# Sheet1-multi.net
KiCad netlist of a schematic drawn in Altium Designer
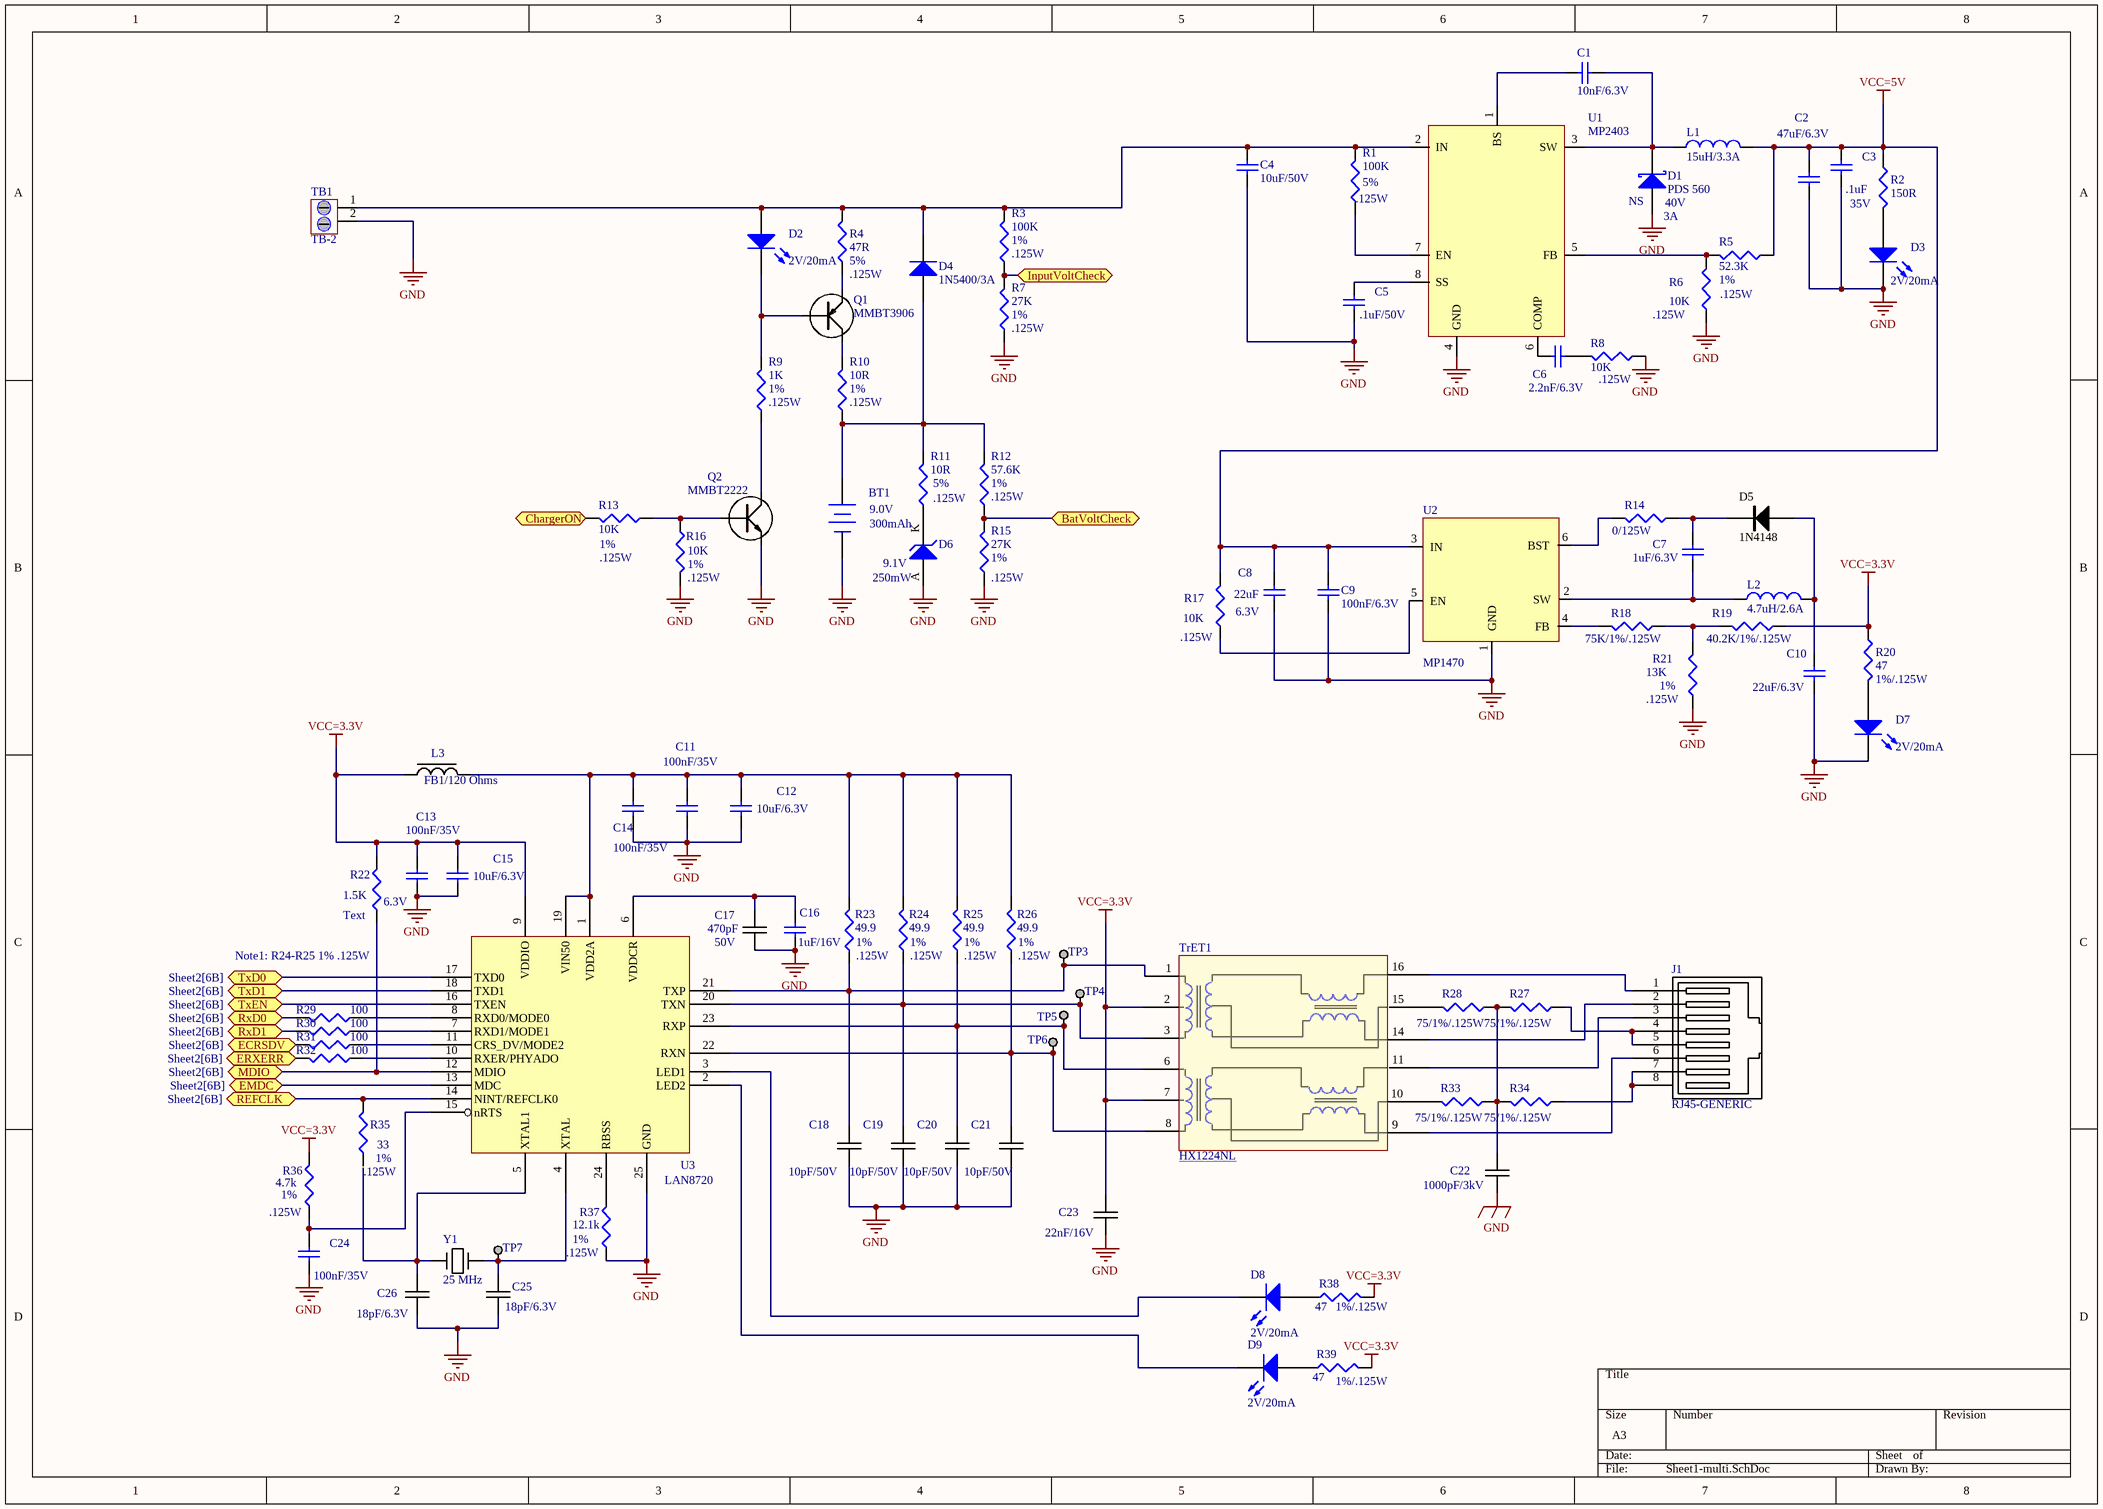
[diagram p0: Sheet1-multi.SchDoc]

(export (version "E")
  (design (tool "Eeschema 10.0.6"))
  (components
    (comp (ref "BT1")
      (value "9.0V")
      (footprint "BAT-2")
      (description "Multicell Battery")
      (fields
        (field (name "MANUFACTURER") "Guangdons China")
        (field (name "PUBLISHER") "sunbangpower.en.alibaba.com")
      )
      (libsource (lib "Miscellaneous Devices") (part "Battery"))
    )
    (comp (ref "C1")
      (value "10nF/6.3V")
      (footprint "0402C-GENERIC")
      (description "Capacitor")
      (fields (field (name "MANUFACTURER") "Murata") (field (name "PUBLISHER") "Altium Limited"))
      (libsource (lib "Miscellaneous Devices") (part "Cap"))
    )
    (comp (ref "C2")
      (value "47uF/6.3V")
      (footprint "1210C-GENERIC")
      (description "Capacitor")
      (fields (field (name "MANUFACTURER") "Murata") (field (name "PUBLISHER") "Altium Limited"))
      (libsource (lib "Miscellaneous Devices") (part "Cap"))
    )
    (comp (ref "C3")
      (value ".1uF")
      (footprint "0402C-GENERIC")
      (description "Capacitor")
      (fields (field (name "MANUFACTURER") "Yaiyo Yuden") (field (name "PUBLISHER") "Altium Limited"))
      (libsource (lib "Miscellaneous Devices") (part "Cap"))
    )
    (comp (ref "C4")
      (value "10uF/50V")
      (footprint "1206C-GENERIC")
      (description "Capacitor")
      (fields (field (name "MANUFACTURER") "Murata") (field (name "PUBLISHER") "Altium Limited"))
      (libsource (lib "Miscellaneous Devices") (part "Cap"))
    )
    (comp (ref "C5")
      (value ".1uF/50V")
      (footprint "0402C-GENERIC")
      (description "Capacitor")
      (fields (field (name "MANUFACTURER") "Murata") (field (name "PUBLISHER") "Altium Limited"))
      (libsource (lib "Miscellaneous Devices") (part "Cap"))
    )
    (comp (ref "C6")
      (value "2.2nF/6.3V")
      (footprint "0402C-GENERIC")
      (description "Capacitor")
      (fields (field (name "MANUFACTURER") "Murata") (field (name "PUBLISHER") "Altium Limited"))
      (libsource (lib "Miscellaneous Devices") (part "Cap"))
    )
    (comp (ref "C7")
      (value "1uF/6.3V")
      (footprint "0603C-GENERIC")
      (description "Capacitor")
      (fields (field (name "MANUFACTURER") "TDK Corporation") (field (name "PUBLISHER") "Altium Limited"))
      (libsource (lib "Miscellaneous Devices") (part "Cap"))
    )
    (comp (ref "C8")
      (value "22uF")
      (footprint "1206C-GENERIC")
      (description "Capacitor")
      (fields (field (name "MANUFACTURER") "Murata") (field (name "PUBLISHER") "Altium Limited"))
      (libsource (lib "Miscellaneous Devices") (part "Cap"))
    )
    (comp (ref "C9")
      (value "100nF/6.3V")
      (footprint "0805C-GENERIC")
      (description "Capacitor")
      (fields (field (name "MANUFACTURER") "Kemet") (field (name "PUBLISHER") "Altium Limited"))
      (libsource (lib "Miscellaneous Devices") (part "Cap"))
    )
    (comp (ref "C10")
      (value "22uF/6.3V")
      (footprint "1206C-GENERIC")
      (description "Capacitor")
      (fields (field (name "MANUFACTURER") "Murata") (field (name "PUBLISHER") "Altium Limited"))
      (libsource (lib "Miscellaneous Devices") (part "Cap"))
    )
    (comp (ref "C11")
      (value "100nF/35V")
      (footprint "0402C-GENERIC")
      (description "Capacitor")
      (fields (field (name "MANUFACTURER") "Yaiyo Yuden") (field (name "PUBLISHER") "Altium Limited"))
      (libsource (lib "Miscellaneous Devices") (part "Cap"))
    )
    (comp (ref "C12")
      (value "10uF/6.3V")
      (footprint "0402C-GENERIC")
      (description "Capacitor")
      (fields (field (name "MANUFACTURER") "Murata") (field (name "PUBLISHER") "Altium Limited"))
      (libsource (lib "Miscellaneous Devices") (part "Cap"))
    )
    (comp (ref "C13")
      (value "100nF/35V")
      (footprint "0402C-GENERIC")
      (description "Capacitor")
      (fields (field (name "MANUFACTURER") "Yaiyo Yuden") (field (name "PUBLISHER") "Altium Limited"))
      (libsource (lib "Miscellaneous Devices") (part "Cap"))
    )
    (comp (ref "C14")
      (value "100nF/35V")
      (footprint "0402C-GENERIC")
      (description "Capacitor")
      (fields (field (name "MANUFACTURER") "Yaiyo Yuden") (field (name "PUBLISHER") "Altium Limited"))
      (libsource (lib "Miscellaneous Devices") (part "Cap"))
    )
    (comp (ref "C15")
      (value "10uF/6.3V")
      (footprint "0402C-GENERIC")
      (description "Capacitor")
      (fields (field (name "MANUFACTURER") "Murata") (field (name "PUBLISHER") "Altium Limited"))
      (libsource (lib "Miscellaneous Devices") (part "Cap"))
    )
    (comp (ref "C16")
      (value "1uF/16V")
      (footprint "0402C-GENERIC")
      (description "Capacitor")
      (fields (field (name "MANUFACTURER") "TDK Corporation") (field (name "PUBLISHER") "Altium Limited"))
      (libsource (lib "Miscellaneous Devices") (part "Cap"))
    )
    (comp (ref "C17")
      (value "470pF")
      (footprint "0402C-GENERIC")
      (description "CAPACITOR 0805 CERAMIC")
      (fields (field (name "MANUFACTURER") "Murata"))
      (libsource (lib "vh_altium_library") (part "0805C-18PF-50V-C0G-JOH"))
    )
    (comp (ref "C18")
      (value "10pF/50V")
      (footprint "0402C-GENERIC")
      (description "CAPACITOR 0805 CERAMIC")
      (fields (field (name "MANUFACTURER") "Murata"))
      (libsource (lib "vh_altium_library") (part "0805C-18PF-50V-C0G-JOH"))
    )
    (comp (ref "C19")
      (value "10pF/50V")
      (footprint "0402C-GENERIC")
      (description "CAPACITOR 0805 CERAMIC")
      (fields (field (name "MANUFACTURER") "Murata"))
      (libsource (lib "vh_altium_library") (part "0805C-18PF-50V-C0G-JOH"))
    )
    (comp (ref "C20")
      (value "10pF/50V")
      (footprint "0402C-GENERIC")
      (description "CAPACITOR 0805 CERAMIC")
      (fields (field (name "MANUFACTURER") "Murata"))
      (libsource (lib "vh_altium_library") (part "0805C-18PF-50V-C0G-JOH"))
    )
    (comp (ref "C21")
      (value "10pF/50V")
      (footprint "0402C-GENERIC")
      (description "CAPACITOR 0805 CERAMIC")
      (fields (field (name "MANUFACTURER") "Murata"))
      (libsource (lib "vh_altium_library") (part "0805C-18PF-50V-C0G-JOH"))
    )
    (comp (ref "C22")
      (value "1000pF/3kV")
      (footprint "1808")
      (description "CAPACITOR 1808CERAMIC")
      (fields (field (name "MANUFACTURER") "Johanson Dielctrics Inc"))
      (libsource (lib "vh_altium_library") (part "0805C-18PF-50V-C0G-JOH"))
    )
    (comp (ref "C23")
      (value "22nF/16V")
      (footprint "0402C-GENERIC")
      (description "CAPACITOR 0805 CERAMIC")
      (fields (field (name "MANUFACTURER") "Murata Electronics"))
      (libsource (lib "vh_altium_library") (part "0805C-18PF-50V-C0G-JOH"))
    )
    (comp (ref "C24")
      (value "100nF/35V")
      (footprint "0402C-GENERIC")
      (description "Capacitor")
      (fields (field (name "MANUFACTURER") "Yaiyo Yuden") (field (name "PUBLISHER") "Altium Limited"))
      (libsource (lib "Miscellaneous Devices") (part "Cap"))
    )
    (comp (ref "C25")
      (value "18pF/6.3V")
      (footprint "0805C-TBD")
      (description "CAPACITOR 0805 CERAMIC")
      (fields (field (name "MANUFACTURER") "Kemet"))
      (libsource (lib "vh_altium_library") (part "0805C-18PF-50V-C0G-JOH"))
    )
    (comp (ref "C26")
      (value "18pF/6.3V")
      (footprint "0805C-TBD")
      (description "CAPACITOR 0805 CERAMIC")
      (fields (field (name "MANUFACTURER") "Kemet"))
      (libsource (lib "vh_altium_library") (part "0805C-18PF-50V-C0G-JOH"))
    )
    (comp (ref "D1")
      (value "PDS 560")
      (footprint "SMB")
      (description "Schottky Diode")
      (fields (field (name "MANUFACTURER") "Diodes Incorporated") (field (name "PUBLISHER") "Altium Limited"))
      (libsource (lib "Miscellaneous Devices") (part "D Schottky"))
    )
    (comp (ref "D2")
      (value "2V/20mA")
      (footprint "LED-SM")
      (description "Typical RED, GREEN, YELLOW, AMBER GaAs LED")
      (fields (field (name "MANUFACTURER") "Lite-On Inc") (field (name "PUBLISHER") "Altium Limited"))
      (libsource (lib "Miscellaneous Devices") (part "LED2"))
    )
    (comp (ref "D3")
      (value "2V/20mA")
      (footprint "LED-SM")
      (description "Typical RED, GREEN, YELLOW, AMBER GaAs LED")
      (fields (field (name "MANUFACTURER") "Lite-On Inc") (field (name "PUBLISHER") "Altium Limited"))
      (libsource (lib "Miscellaneous Devices") (part "LED2"))
    )
    (comp (ref "D4")
      (value "1N5400/3A")
      (footprint "DO-41")
      (description "1 Amp General Purpose Rectifier")
      (fields (field (name "MANUFACTURER") "NTE Electronics") (field (name "PUBLISHER") "Altium Limited"))
      (libsource (lib "Miscellaneous Devices") (part "Diode 1N4007"))
    )
    (comp (ref "D5")
      (value "1N4148")
      (footprint "SOD-123")
      (description "1N4001")
      (fields (field (name "MANUFACTURER") "Vishay"))
      (libsource (lib "vh_altium_library") (part "1N4001"))
    )
    (comp (ref "D6")
      (value "9.1V")
      (footprint "SOT23-DIODE")
      (description "Zener Diode")
      (fields (field (name "MANUFACTURER") "NXP Semi") (field (name "PUBLISHER") "Altium Limited"))
      (libsource (lib "Miscellaneous Devices") (part "D Zener"))
    )
    (comp (ref "D7")
      (value "2V/20mA")
      (footprint "LED-SM")
      (description "Typical RED, GREEN, YELLOW, AMBER GaAs LED")
      (fields (field (name "MANUFACTURER") "Lite-On Inc") (field (name "PUBLISHER") "Altium Limited"))
      (libsource (lib "Miscellaneous Devices") (part "LED2"))
    )
    (comp (ref "D8")
      (value "2V/20mA")
      (footprint "LED-SM")
      (description "Typical RED, GREEN, YELLOW, AMBER GaAs LED")
      (fields (field (name "MANUFACTURER") "Lite-On Inc") (field (name "PUBLISHER") "Altium Limited"))
      (libsource (lib "Miscellaneous Devices") (part "LED2"))
    )
    (comp (ref "D9")
      (value "2V/20mA")
      (footprint "LED-SM")
      (description "Typical RED, GREEN, YELLOW, AMBER GaAs LED")
      (fields (field (name "MANUFACTURER") "Lite-On Inc") (field (name "PUBLISHER") "Altium Limited"))
      (libsource (lib "Miscellaneous Devices") (part "LED2"))
    )
    (comp (ref "J1")
      (value "RJ45-GENERIC")
      (footprint "RJ45-8/8")
      (description "GENERIC RJ45 CONNECTOR 8 PIN")
      (fields (field (name "MANUFACTURER") "Assman WSW Components"))
      (libsource (lib "vh_altium_library") (part "RJ45-GENERIC"))
    )
    (comp (ref "L1")
      (value "15uH/3.3A")
      (footprint "Murata 15uH inductor")
      (description "Inductor")
      (fields (field (name "MANUFACTURER") "Murata") (field (name "PUBLISHER") "Altium Limited"))
      (libsource (lib "Miscellaneous Devices") (part "Inductor"))
    )
    (comp (ref "L2")
      (value "4.7uH/2.6A")
      (footprint "Inductor 4.7/6.8")
      (description "Inductor")
      (fields (field (name "MANUFACTURER") "Bourns") (field (name "PUBLISHER") "Altium Limited"))
      (libsource (lib "Miscellaneous Devices") (part "Inductor"))
    )
    (comp (ref "L3")
      (value "FB1/120 Ohms")
      (footprint "0603C-2U2")
      (description "1239AS-H-1R0N")
      (fields (field (name "MANUFACTURER") "Murata Electronics"))
      (libsource (lib "SMD Magnetics-SM") (part "1U-1239AS-TOKO"))
    )
    (comp (ref "Q1")
      (value "MMBT3906")
      (footprint "SOT23-BCE")
      (description "GENERIC PNP BIPOLAR TRANSISTOR")
      (fields (field (name "MANUFACTURER") "On Semi"))
      (libsource (lib "generic") (part "PNP-GENERIC"))
    )
    (comp (ref "Q2")
      (value "MMBT2222")
      (footprint "MMBT2222")
      (description "BC847 SMALL SIGNAL NPN TRANSISTOR")
      (fields (field (name "MANUFACTURER") "Diodes  Inc."))
      (libsource (lib "vh_altium_library") (part "MMBT2222"))
    )
    (comp (ref "R1")
      (value "100K")
      (footprint "0402R-TBD")
      (description "Resistor")
      (fields (field (name "MANUFACTURER") "Panasonic") (field (name "PUBLISHER") "Altium Limited"))
      (libsource (lib "Miscellaneous Devices") (part "Res3"))
    )
    (comp (ref "R2")
      (value "150R")
      (footprint "0402R-TBD")
      (description "Resistor")
      (fields (field (name "PUBLISHER") "Altium Limited"))
      (libsource (lib "Miscellaneous Devices") (part "Res3"))
    )
    (comp (ref "R3")
      (value "100K")
      (footprint "0402R-TBD")
      (description "Resistor")
      (fields (field (name "MANUFACTURER") "Panasonic") (field (name "PUBLISHER") "Altium Limited"))
      (libsource (lib "Miscellaneous Devices") (part "Res3"))
    )
    (comp (ref "R4")
      (value "47R")
      (footprint "0402R-TBD")
      (description "Resistor")
      (fields
        (field (name "MANUFACTURER") "Stackpole Electronics Inc")
        (field (name "PUBLISHER") "Altium Limited")
      )
      (libsource (lib "Miscellaneous Devices") (part "Res3"))
    )
    (comp (ref "R5")
      (value "52.3K")
      (footprint "0402R-TBD")
      (description "Resistor")
      (fields (field (name "MANUFACTURER") "Panasonic") (field (name "PUBLISHER") "Altium Limited"))
      (libsource (lib "Miscellaneous Devices") (part "Res3"))
    )
    (comp (ref "R6")
      (value "10K")
      (footprint "0402R-TBD")
      (description "Resistor")
      (fields (field (name "MANUFACTURER") "Panasonic") (field (name "PUBLISHER") "Altium Limited"))
      (libsource (lib "Miscellaneous Devices") (part "Res3"))
    )
    (comp (ref "R7")
      (value "27K")
      (footprint "0402R-TBD")
      (description "Resistor")
      (fields (field (name "MANUFACTURER") "Panasonic") (field (name "PUBLISHER") "Altium Limited"))
      (libsource (lib "Miscellaneous Devices") (part "Res3"))
    )
    (comp (ref "R8")
      (value "10K")
      (footprint "0402R-TBD")
      (description "Resistor")
      (fields (field (name "MANUFACTURER") "Panasonic") (field (name "PUBLISHER") "Altium Limited"))
      (libsource (lib "Miscellaneous Devices") (part "Res3"))
    )
    (comp (ref "R9")
      (value "1K")
      (footprint "0402R-TBD")
      (description "Resistor")
      (fields (field (name "MANUFACTURER") "Panasonic") (field (name "PUBLISHER") "Altium Limited"))
      (libsource (lib "Miscellaneous Devices") (part "Res3"))
    )
    (comp (ref "R10")
      (value "10R")
      (footprint "0402R-TBD")
      (description "Resistor")
      (fields (field (name "MANUFACTURER") "Panasonic") (field (name "PUBLISHER") "Altium Limited"))
      (libsource (lib "Miscellaneous Devices") (part "Res3"))
    )
    (comp (ref "R11")
      (value "10R")
      (footprint "0402R-TBD")
      (description "Resistor")
      (fields (field (name "MANUFACTURER") "Panasonic") (field (name "PUBLISHER") "Altium Limited"))
      (libsource (lib "Miscellaneous Devices") (part "Res3"))
    )
    (comp (ref "R12")
      (value "57.6K")
      (footprint "0402R-TBD")
      (description "Resistor")
      (fields (field (name "MANUFACTURER") "Panasonic") (field (name "PUBLISHER") "Altium Limited"))
      (libsource (lib "Miscellaneous Devices") (part "Res3"))
    )
    (comp (ref "R13")
      (value "10K")
      (footprint "0402R-TBD")
      (description "Resistor")
      (fields (field (name "MANUFACTURER") "Panasonic") (field (name "PUBLISHER") "Altium Limited"))
      (libsource (lib "Miscellaneous Devices") (part "Res3"))
    )
    (comp (ref "R14")
      (value "0/125W")
      (footprint "0805R-0R1")
      (description "Resistor")
      (fields (field (name "MANUFACTURER") "Vishay Dale") (field (name "PUBLISHER") "Altium Limited"))
      (libsource (lib "Miscellaneous Devices") (part "Res3"))
    )
    (comp (ref "R15")
      (value "27K")
      (footprint "0402R-TBD")
      (description "Resistor")
      (fields (field (name "MANUFACTURER") "Panasonic") (field (name "PUBLISHER") "Altium Limited"))
      (libsource (lib "Miscellaneous Devices") (part "Res3"))
    )
    (comp (ref "R16")
      (value "10K")
      (footprint "0805R-0R1")
      (description "Resistor")
      (fields (field (name "MANUFACTURER") "Samsung") (field (name "PUBLISHER") "Altium Limited"))
      (libsource (lib "Miscellaneous Devices") (part "Res3"))
    )
    (comp (ref "R17")
      (value "10K")
      (footprint "0402R-TBD")
      (description "Resistor")
      (fields (field (name "MANUFACTURER") "Panasonic") (field (name "PUBLISHER") "Altium Limited"))
      (libsource (lib "Miscellaneous Devices") (part "Res3"))
    )
    (comp (ref "R18")
      (value "75K/1%/.125W")
      (footprint "0402C-TBD")
      (description "Resistor")
      (fields (field (name "MANUFACTURER") "Panasonic") (field (name "PUBLISHER") "Altium Limited"))
      (libsource (lib "Miscellaneous Devices") (part "Res3"))
    )
    (comp (ref "R19")
      (value "40.2K/1%/.125W")
      (footprint "0402R-TBD")
      (description "Resistor")
      (fields (field (name "MANUFACTURER") "Panasonic") (field (name "PUBLISHER") "Altium Limited"))
      (libsource (lib "Miscellaneous Devices") (part "Res3"))
    )
    (comp (ref "R20")
      (value "47")
      (footprint "0402R-TBD")
      (description "Resistor")
      (fields (field (name "PUBLISHER") "Altium Limited"))
      (libsource (lib "Miscellaneous Devices") (part "Res3"))
    )
    (comp (ref "R21")
      (value "13K")
      (footprint "0402R-TBD")
      (description "Resistor")
      (fields (field (name "MANUFACTURER") "Panasonic") (field (name "PUBLISHER") "Altium Limited"))
      (libsource (lib "Miscellaneous Devices") (part "Res3"))
    )
    (comp (ref "R22")
      (value "1.5K")
      (footprint "0402R-TBD")
      (description "Resistor")
      (fields (field (name "MANUFACTURER") "Panasonic") (field (name "PUBLISHER") "Altium Limited"))
      (libsource (lib "Miscellaneous Devices") (part "Res3"))
    )
    (comp (ref "R23")
      (value "49.9")
      (footprint "0402R-TBD")
      (description "Resistor")
      (fields (field (name "MANUFACTURER") "Panasonic") (field (name "PUBLISHER") "Altium Limited"))
      (libsource (lib "Miscellaneous Devices") (part "Res3"))
    )
    (comp (ref "R24")
      (value "49.9")
      (footprint "0402R-TBD")
      (description "Resistor")
      (fields (field (name "MANUFACTURER") "Panasonic") (field (name "PUBLISHER") "Altium Limited"))
      (libsource (lib "Miscellaneous Devices") (part "Res3"))
    )
    (comp (ref "R25")
      (value "49.9")
      (footprint "0402R-TBD")
      (description "Resistor")
      (fields (field (name "MANUFACTURER") "Panasonic") (field (name "PUBLISHER") "Altium Limited"))
      (libsource (lib "Miscellaneous Devices") (part "Res3"))
    )
    (comp (ref "R26")
      (value "49.9")
      (footprint "0402R-TBD")
      (description "Resistor")
      (fields (field (name "MANUFACTURER") "Panasonic") (field (name "PUBLISHER") "Altium Limited"))
      (libsource (lib "Miscellaneous Devices") (part "Res3"))
    )
    (comp (ref "R27")
      (value "75/1%/.125W")
      (footprint "0402R-TBD")
      (description "Resistor")
      (fields (field (name "MANUFACTURER") "Panasonic") (field (name "PUBLISHER") "Altium Limited"))
      (libsource (lib "Miscellaneous Devices") (part "Res3"))
    )
    (comp (ref "R28")
      (value "75/1%/.125W")
      (footprint "0402R-TBD")
      (description "Resistor")
      (fields (field (name "MANUFACTURER") "Panasonic") (field (name "PUBLISHER") "Altium Limited"))
      (libsource (lib "Miscellaneous Devices") (part "Res3"))
    )
    (comp (ref "R29")
      (value "100")
      (footprint "0402R-TBD")
      (description "Resistor")
      (fields (field (name "MANUFACTURER") "Panasonic") (field (name "PUBLISHER") "Altium Limited"))
      (libsource (lib "Miscellaneous Devices") (part "Res3"))
    )
    (comp (ref "R30")
      (value "100")
      (footprint "0402R-TBD")
      (description "Resistor")
      (fields (field (name "MANUFACTURER") "Panasonic") (field (name "PUBLISHER") "Altium Limited"))
      (libsource (lib "Miscellaneous Devices") (part "Res3"))
    )
    (comp (ref "R31")
      (value "100")
      (footprint "0402R-TBD")
      (description "Resistor")
      (fields (field (name "MANUFACTURER") "Panasonic") (field (name "PUBLISHER") "Altium Limited"))
      (libsource (lib "Miscellaneous Devices") (part "Res3"))
    )
    (comp (ref "R32")
      (value "100")
      (footprint "0402R-TBD")
      (description "Resistor")
      (fields (field (name "MANUFACTURER") "Panasonic") (field (name "PUBLISHER") "Altium Limited"))
      (libsource (lib "Miscellaneous Devices") (part "Res3"))
    )
    (comp (ref "R33")
      (value "75/1%/.125W")
      (footprint "0402R-TBD")
      (description "Resistor")
      (fields (field (name "MANUFACTURER") "Panasonic") (field (name "PUBLISHER") "Altium Limited"))
      (libsource (lib "Miscellaneous Devices") (part "Res3"))
    )
    (comp (ref "R34")
      (value "75/1%/.125W")
      (footprint "0402R-TBD")
      (description "Resistor")
      (fields (field (name "MANUFACTURER") "Panasonic") (field (name "PUBLISHER") "Altium Limited"))
      (libsource (lib "Miscellaneous Devices") (part "Res3"))
    )
    (comp (ref "R35")
      (value "33")
      (footprint "0402R-TBD")
      (description "Resistor")
      (fields (field (name "MANUFACTURER") "Panasonic") (field (name "PUBLISHER") "Altium Limited"))
      (libsource (lib "Miscellaneous Devices") (part "Res3"))
    )
    (comp (ref "R36")
      (value "4.7k")
      (footprint "0402R-TBD")
      (description "Resistor")
      (fields (field (name "MANUFACTURER") "Panasonic") (field (name "PUBLISHER") "Altium Limited"))
      (libsource (lib "Miscellaneous Devices") (part "Res3"))
    )
    (comp (ref "R37")
      (value "12.1k")
      (footprint "0402R-TBD")
      (description "Resistor")
      (fields (field (name "MANUFACTURER") "Panasonic") (field (name "PUBLISHER") "Altium Limited"))
      (libsource (lib "Miscellaneous Devices") (part "Res3"))
    )
    (comp (ref "R38")
      (value "47")
      (footprint "0402R-TBD")
      (description "Resistor")
      (fields (field (name "PUBLISHER") "Altium Limited"))
      (libsource (lib "Miscellaneous Devices") (part "Res3"))
    )
    (comp (ref "R39")
      (value "47")
      (footprint "0402R-TBD")
      (description "Resistor")
      (fields (field (name "PUBLISHER") "Altium Limited"))
      (libsource (lib "Miscellaneous Devices") (part "Res3"))
    )
    (comp (ref "TB1")
      (value "TB-2")
      (footprint "Terminal Block 2x5mm")
      (fields (field (name "MANUFACTURER") "On Store Technology"))
      (libsource (lib "SMLib") (part "TB-2"))
    )
    (comp (ref "TP3")
      (value "TESTPOINT")
      (footprint "TESTPOINT")
      (description "TESTPOINT SCOPE GRABBER")
      (fields
        (field (name "MANUFACTURER PART NUMBER") "5010")
        (field (name "MANUFACTURER") "Keystone Electronics")
      )
      (libsource (lib "vh_altium_library") (part "TESTPOINT"))
    )
    (comp (ref "TP4")
      (value "TESTPOINT")
      (footprint "TESTPOINT")
      (description "TESTPOINT SCOPE GRABBER")
      (fields
        (field (name "MANUFACTURER PART NUMBER") "5010")
        (field (name "MANUFACTURER") "Keystone Electronics")
      )
      (libsource (lib "vh_altium_library") (part "TESTPOINT"))
    )
    (comp (ref "TP5")
      (value "TESTPOINT")
      (footprint "TESTPOINT")
      (description "TESTPOINT SCOPE GRABBER")
      (fields
        (field (name "MANUFACTURER PART NUMBER") "5010")
        (field (name "MANUFACTURER") "Keystone Electronics")
      )
      (libsource (lib "vh_altium_library") (part "TESTPOINT"))
    )
    (comp (ref "TP6")
      (value "TESTPOINT")
      (footprint "TESTPOINT")
      (description "TESTPOINT SCOPE GRABBER")
      (fields
        (field (name "MANUFACTURER PART NUMBER") "5010")
        (field (name "MANUFACTURER") "Keystone Electronics")
      )
      (libsource (lib "vh_altium_library") (part "TESTPOINT"))
    )
    (comp (ref "TP7")
      (value "TESTPOINT")
      (footprint "TESTPOINT")
      (description "TESTPOINT SCOPE GRABBER")
      (fields
        (field (name "MANUFACTURER PART NUMBER") "5010")
        (field (name "MANUFACTURER") "Keystone Electronics")
      )
      (libsource (lib "vh_altium_library") (part "TESTPOINT"))
    )
    (comp (ref "TrET1")
      (value "HX1224NL")
      (footprint "S558-5999-Ethtransf")
      (fields (field (name "MANUFACTURER") "Bel Fuse Inc"))
      (libsource (lib "SMLib") (part "S558-5999-Eth.TR"))
    )
    (comp (ref "U1")
      (value "MP2403")
      (footprint "MP2403")
      (fields (field (name "MANUFACTURER") "MPS Inc"))
      (libsource (lib "SMLib") (part "MP2403"))
    )
    (comp (ref "U2")
      (value "MP1470")
      (footprint "MP1470")
      (fields (field (name "MANUFACTURER") "MPS Inc"))
      (libsource (lib "SMLib") (part "MP1470"))
    )
    (comp (ref "U3")
      (value "LAN8720")
      (footprint "Atmel Multimedia:QFN24_4X4_N")
      (fields (field (name "MANUFACTURER") "Microchip"))
      (libsource (lib "SMLib") (part "LAN8720"))
    )
    (comp (ref "Y1")
      (value "25 MHz")
      (footprint "25Mhz-oscl")
      (description "GENERIC CRYSTAL")
      (fields (field (name "MANUFACTURER") "Arbacon"))
      (libsource (lib "vh_altium_library") (part "CRYSTAL-GENERIC"))
    )
  )
  (nets
    (net (code "1") (name "/BatVoltCheck") (class "Default")
      (node (ref "R12") (pin "1") (pinfunction "1_1") (pintype "passive"))
      (node (ref "R15") (pin "2") (pinfunction "2_2") (pintype "passive"))
    )
    (net (code "2") (name "/ChargerON") (class "Default")
      (node (ref "R13") (pin "2") (pinfunction "2_2") (pintype "passive"))
    )
    (net (code "3") (name "/ECRSDV") (class "Default")
      (node (ref "R31") (pin "2") (pinfunction "2_2") (pintype "passive"))
    )
    (net (code "4") (name "/EMDC") (class "Default")
      (node (ref "U3") (pin "13") (pinfunction "MDC_13") (pintype "passive"))
    )
    (net (code "5") (name "/ERXERR") (class "Default")
      (node (ref "R32") (pin "2") (pinfunction "2_2") (pintype "passive"))
    )
    (net (code "6") (name "/InputVoltCheck") (class "Default")
      (node (ref "R3") (pin "1") (pinfunction "1_1") (pintype "passive"))
      (node (ref "R7") (pin "2") (pinfunction "2_2") (pintype "passive"))
    )
    (net (code "7") (name "/MDIO") (class "Default")
      (node (ref "R22") (pin "1") (pinfunction "1_1") (pintype "passive"))
      (node (ref "U3") (pin "12") (pinfunction "MDIO_12") (pintype "passive"))
    )
    (net (code "8") (name "/REFCLK") (class "Default")
      (node (ref "R35") (pin "2") (pinfunction "2_2") (pintype "passive"))
      (node (ref "U3") (pin "14") (pinfunction "NINT/REFCLK0_14") (pintype "passive"))
    )
    (net (code "9") (name "/RxD0") (class "Default")
      (node (ref "R29") (pin "2") (pinfunction "2_2") (pintype "passive"))
    )
    (net (code "10") (name "/RxD1") (class "Default")
      (node (ref "R30") (pin "2") (pinfunction "2_2") (pintype "passive"))
    )
    (net (code "11") (name "/TxD0") (class "Default")
      (node (ref "U3") (pin "17") (pinfunction "TXD0_17") (pintype "passive"))
    )
    (net (code "12") (name "/TxD1") (class "Default")
      (node (ref "U3") (pin "18") (pinfunction "TXD1_18") (pintype "passive"))
    )
    (net (code "13") (name "/TxEN") (class "Default")
      (node (ref "U3") (pin "16") (pinfunction "TXEN_16") (pintype "passive"))
    )
    (net (code "14") (name "GND") (class "Default")
      (node (ref "BT1") (pin "2") (pinfunction "-_2") (pintype "passive"))
      (node (ref "C10") (pin "2") (pinfunction "2_2") (pintype "passive"))
      (node (ref "C11") (pin "2") (pinfunction "2_2") (pintype "passive"))
      (node (ref "C12") (pin "2") (pinfunction "2_2") (pintype "passive"))
      (node (ref "C13") (pin "2") (pinfunction "2_2") (pintype "passive"))
      (node (ref "C14") (pin "2") (pinfunction "2_2") (pintype "passive"))
      (node (ref "C15") (pin "2") (pinfunction "2_2") (pintype "passive"))
      (node (ref "C16") (pin "2") (pinfunction "2_2") (pintype "passive"))
      (node (ref "C17") (pin "2") (pintype "passive"))
      (node (ref "C18") (pin "2") (pintype "passive"))
      (node (ref "C19") (pin "2") (pintype "passive"))
      (node (ref "C2") (pin "2") (pinfunction "2_2") (pintype "passive"))
      (node (ref "C20") (pin "2") (pintype "passive"))
      (node (ref "C21") (pin "2") (pintype "passive"))
      (node (ref "C22") (pin "2") (pintype "passive"))
      (node (ref "C23") (pin "2") (pintype "passive"))
      (node (ref "C24") (pin "2") (pinfunction "2_2") (pintype "passive"))
      (node (ref "C25") (pin "2") (pintype "passive"))
      (node (ref "C26") (pin "2") (pintype "passive"))
      (node (ref "C3") (pin "2") (pinfunction "2_2") (pintype "passive"))
      (node (ref "C4") (pin "2") (pinfunction "2_2") (pintype "passive"))
      (node (ref "C5") (pin "2") (pinfunction "2_2") (pintype "passive"))
      (node (ref "C8") (pin "2") (pinfunction "2_2") (pintype "passive"))
      (node (ref "C9") (pin "1") (pinfunction "1_1") (pintype "passive"))
      (node (ref "D1") (pin "1") (pinfunction "A_1") (pintype "passive"))
      (node (ref "D3") (pin "2") (pinfunction "K_2") (pintype "passive"))
      (node (ref "D6") (pin "A") (pinfunction "A_A") (pintype "passive"))
      (node (ref "D7") (pin "2") (pinfunction "K_2") (pintype "passive"))
      (node (ref "Q2") (pin "E") (pintype "passive"))
      (node (ref "R15") (pin "1") (pinfunction "1_1") (pintype "passive"))
      (node (ref "R16") (pin "2") (pinfunction "2_2") (pintype "passive"))
      (node (ref "R21") (pin "1") (pinfunction "1_1") (pintype "passive"))
      (node (ref "R37") (pin "1") (pinfunction "1_1") (pintype "passive"))
      (node (ref "R6") (pin "1") (pinfunction "1_1") (pintype "passive"))
      (node (ref "R7") (pin "1") (pinfunction "1_1") (pintype "passive"))
      (node (ref "R8") (pin "1") (pinfunction "1_1") (pintype "passive"))
      (node (ref "TB1") (pin "2") (pinfunction "2_2") (pintype "passive"))
      (node (ref "U1") (pin "4") (pinfunction "GND_4") (pintype "passive"))
      (node (ref "U2") (pin "1") (pinfunction "GND_1") (pintype "passive"))
      (node (ref "U3") (pin "25") (pinfunction "GND_25") (pintype "passive"))
    )
    (net (code "15") (name "Net-(BT1-+)") (class "Default")
      (node (ref "BT1") (pin "1") (pinfunction "+_1") (pintype "passive"))
      (node (ref "D4") (pin "1") (pinfunction "A_1") (pintype "passive"))
      (node (ref "R10") (pin "1") (pinfunction "1_1") (pintype "passive"))
      (node (ref "R11") (pin "2") (pinfunction "2_2") (pintype "passive"))
      (node (ref "R12") (pin "2") (pinfunction "2_2") (pintype "passive"))
    )
    (net (code "16") (name "Net-(C6-Pad2)") (class "Default")
      (node (ref "C6") (pin "2") (pinfunction "2_2") (pintype "passive"))
      (node (ref "R8") (pin "2") (pinfunction "2_2") (pintype "passive"))
    )
    (net (code "17") (name "Net-(C7-Pad1)") (class "Default")
      (node (ref "C7") (pin "1") (pinfunction "1_1") (pintype "passive"))
      (node (ref "D5") (pin "K") (pinfunction "K_K") (pintype "passive"))
      (node (ref "R14") (pin "1") (pinfunction "1_1") (pintype "passive"))
    )
    (net (code "18") (name "Net-(C10-Pad1)") (class "Default")
      (node (ref "C10") (pin "1") (pinfunction "1_1") (pintype "passive"))
      (node (ref "D5") (pin "A") (pinfunction "A_A") (pintype "passive"))
      (node (ref "L2") (pin "2") (pinfunction "2_2") (pintype "passive"))
    )
    (net (code "19") (name "Net-(C22-Pad1)") (class "Default")
      (node (ref "C22") (pin "1") (pintype "passive"))
      (node (ref "R27") (pin "2") (pinfunction "2_2") (pintype "passive"))
      (node (ref "R28") (pin "1") (pinfunction "1_1") (pintype "passive"))
      (node (ref "R33") (pin "1") (pinfunction "1_1") (pintype "passive"))
      (node (ref "R34") (pin "2") (pinfunction "2_2") (pintype "passive"))
    )
    (net (code "20") (name "Net-(D1-K)") (class "Default")
      (node (ref "C1") (pin "2") (pinfunction "2_2") (pintype "passive"))
      (node (ref "D1") (pin "2") (pinfunction "K_2") (pintype "passive"))
      (node (ref "L1") (pin "1") (pinfunction "1_1") (pintype "passive"))
      (node (ref "U1") (pin "3") (pinfunction "SW_3") (pintype "passive"))
    )
    (net (code "21") (name "Net-(D2-A)") (class "Default")
      (node (ref "C4") (pin "1") (pinfunction "1_1") (pintype "passive"))
      (node (ref "D2") (pin "1") (pinfunction "A_1") (pintype "passive"))
      (node (ref "D4") (pin "2") (pinfunction "K_2") (pintype "passive"))
      (node (ref "R1") (pin "2") (pinfunction "2_2") (pintype "passive"))
      (node (ref "R3") (pin "2") (pinfunction "2_2") (pintype "passive"))
      (node (ref "R4") (pin "2") (pinfunction "2_2") (pintype "passive"))
      (node (ref "TB1") (pin "1") (pinfunction "1_1") (pintype "passive"))
      (node (ref "U1") (pin "2") (pinfunction "IN_2") (pintype "passive"))
    )
    (net (code "22") (name "Net-(D2-K)") (class "Default")
      (node (ref "D2") (pin "2") (pinfunction "K_2") (pintype "passive"))
      (node (ref "Q1") (pin "B") (pintype "passive"))
      (node (ref "R9") (pin "2") (pinfunction "2_2") (pintype "passive"))
    )
    (net (code "23") (name "Net-(D3-A)") (class "Default")
      (node (ref "D3") (pin "1") (pinfunction "A_1") (pintype "passive"))
      (node (ref "R2") (pin "2") (pinfunction "2_2") (pintype "passive"))
    )
    (net (code "24") (name "Net-(D6-PadK)") (class "Default")
      (node (ref "D6") (pin "K") (pinfunction "K_K") (pintype "passive"))
      (node (ref "R11") (pin "1") (pinfunction "1_1") (pintype "passive"))
    )
    (net (code "25") (name "Net-(D7-A)") (class "Default")
      (node (ref "D7") (pin "1") (pinfunction "A_1") (pintype "passive"))
      (node (ref "R20") (pin "2") (pinfunction "2_2") (pintype "passive"))
    )
    (net (code "26") (name "Net-(D8-A)") (class "Default")
      (node (ref "D8") (pin "1") (pinfunction "A_1") (pintype "passive"))
      (node (ref "R38") (pin "1") (pinfunction "1_1") (pintype "passive"))
    )
    (net (code "27") (name "Net-(D8-K)") (class "Default")
      (node (ref "D8") (pin "2") (pinfunction "K_2") (pintype "passive"))
      (node (ref "U3") (pin "3") (pinfunction "LED1_3") (pintype "passive"))
    )
    (net (code "28") (name "Net-(D9-A)") (class "Default")
      (node (ref "D9") (pin "1") (pinfunction "A_1") (pintype "passive"))
      (node (ref "R39") (pin "1") (pinfunction "1_1") (pintype "passive"))
    )
    (net (code "29") (name "Net-(D9-K)") (class "Default")
      (node (ref "D9") (pin "2") (pinfunction "K_2") (pintype "passive"))
      (node (ref "U3") (pin "2") (pinfunction "LED2_2") (pintype "passive"))
    )
    (net (code "30") (name "Net-(J1-Pad2)") (class "Default")
      (node (ref "J1") (pin "2") (pintype "passive"))
      (node (ref "TrET1") (pin "14") (pintype "passive"))
    )
    (net (code "31") (name "Net-(J1-Pad4)") (class "Default")
      (node (ref "J1") (pin "4") (pintype "passive"))
      (node (ref "J1") (pin "5") (pintype "passive"))
      (node (ref "R27") (pin "1") (pinfunction "1_1") (pintype "passive"))
    )
    (net (code "32") (name "Net-(J1-Pad7)") (class "Default")
      (node (ref "J1") (pin "7") (pintype "passive"))
      (node (ref "J1") (pin "8") (pintype "passive"))
      (node (ref "R34") (pin "1") (pinfunction "1_1") (pintype "passive"))
    )
    (net (code "33") (name "Net-(Q1-PadC)") (class "Default")
      (node (ref "Q1") (pin "C") (pintype "passive"))
      (node (ref "R10") (pin "2") (pinfunction "2_2") (pintype "passive"))
    )
    (net (code "34") (name "Net-(Q1-PadE)") (class "Default")
      (node (ref "Q1") (pin "E") (pintype "passive"))
      (node (ref "R4") (pin "1") (pinfunction "1_1") (pintype "passive"))
    )
    (net (code "35") (name "Net-(Q2-PadB)") (class "Default")
      (node (ref "Q2") (pin "B") (pintype "passive"))
      (node (ref "R13") (pin "1") (pinfunction "1_1") (pintype "passive"))
      (node (ref "R16") (pin "1") (pinfunction "1_1") (pintype "passive"))
    )
    (net (code "36") (name "Net-(Q2-PadC)") (class "Default")
      (node (ref "Q2") (pin "C") (pintype "passive"))
      (node (ref "R9") (pin "1") (pinfunction "1_1") (pintype "passive"))
    )
    (net (code "37") (name "Net-(R18-Pad1)") (class "Default")
      (node (ref "R18") (pin "1") (pinfunction "1_1") (pintype "passive"))
      (node (ref "R19") (pin "2") (pinfunction "2_2") (pintype "passive"))
      (node (ref "R21") (pin "2") (pinfunction "2_2") (pintype "passive"))
    )
    (net (code "38") (name "Net-(TrET1-11)") (class "Default")
      (node (ref "R28") (pin "2") (pinfunction "2_2") (pintype "passive"))
      (node (ref "TrET1") (pin "15") (pinfunction "11_15") (pintype "passive"))
    )
    (net (code "39") (name "Net-(TrET1-12)") (class "Default")
      (node (ref "J1") (pin "3") (pintype "passive"))
      (node (ref "TrET1") (pin "11") (pinfunction "12_11") (pintype "passive"))
    )
    (net (code "40") (name "Net-(TrET1-13)") (class "Default")
      (node (ref "R33") (pin "2") (pinfunction "2_2") (pintype "passive"))
      (node (ref "TrET1") (pin "10") (pinfunction "13_10") (pintype "passive"))
    )
    (net (code "41") (name "Net-(TrET1-14)") (class "Default")
      (node (ref "J1") (pin "6") (pintype "passive"))
      (node (ref "TrET1") (pin "9") (pinfunction "14_9") (pintype "passive"))
    )
    (net (code "42") (name "Net-(TrET1-16)") (class "Default")
      (node (ref "C20") (pin "1") (pintype "passive"))
      (node (ref "R25") (pin "1") (pinfunction "1_1") (pintype "passive"))
      (node (ref "TP5") (pin "1") (pinfunction "1_1") (pintype "passive"))
      (node (ref "TrET1") (pin "6") (pinfunction "16_6") (pintype "passive"))
      (node (ref "U3") (pin "23") (pinfunction "RXP_23") (pintype "passive"))
    )
    (net (code "43") (name "Net-(TrET1-18)") (class "Default")
      (node (ref "C21") (pin "1") (pintype "passive"))
      (node (ref "R26") (pin "1") (pinfunction "1_1") (pintype "passive"))
      (node (ref "TP6") (pin "1") (pinfunction "1_1") (pintype "passive"))
      (node (ref "TrET1") (pin "8") (pinfunction "18_8") (pintype "passive"))
      (node (ref "U3") (pin "22") (pinfunction "RXN_22") (pintype "passive"))
    )
    (net (code "44") (name "Net-(TrET1-TD+)") (class "Default")
      (node (ref "C18") (pin "1") (pintype "passive"))
      (node (ref "R23") (pin "1") (pinfunction "1_1") (pintype "passive"))
      (node (ref "TP3") (pin "1") (pinfunction "1_1") (pintype "passive"))
      (node (ref "TrET1") (pin "1") (pinfunction "TD+_1") (pintype "passive"))
      (node (ref "U3") (pin "21") (pinfunction "TXP_21") (pintype "passive"))
    )
    (net (code "45") (name "Net-(TrET1-TD-)") (class "Default")
      (node (ref "C19") (pin "1") (pintype "passive"))
      (node (ref "R24") (pin "1") (pinfunction "1_1") (pintype "passive"))
      (node (ref "TP4") (pin "1") (pinfunction "1_1") (pintype "passive"))
      (node (ref "TrET1") (pin "3") (pinfunction "TD-_3") (pintype "passive"))
      (node (ref "U3") (pin "20") (pinfunction "TXN_20") (pintype "passive"))
    )
    (net (code "46") (name "Net-(TrET1-Tx+_16)") (class "Default")
      (node (ref "J1") (pin "1") (pintype "passive"))
      (node (ref "TrET1") (pin "16") (pinfunction "Tx+_16_16") (pintype "passive"))
    )
    (net (code "47") (name "Net-(U1-BS)") (class "Default")
      (node (ref "C1") (pin "1") (pinfunction "1_1") (pintype "passive"))
      (node (ref "U1") (pin "1") (pinfunction "BS_1") (pintype "passive"))
    )
    (net (code "48") (name "Net-(U1-COMP)") (class "Default")
      (node (ref "C6") (pin "1") (pinfunction "1_1") (pintype "passive"))
      (node (ref "U1") (pin "6") (pinfunction "COMP_6") (pintype "passive"))
    )
    (net (code "49") (name "Net-(U1-EN)") (class "Default")
      (node (ref "R1") (pin "1") (pinfunction "1_1") (pintype "passive"))
      (node (ref "U1") (pin "7") (pinfunction "EN_7") (pintype "passive"))
    )
    (net (code "50") (name "Net-(U1-FB)") (class "Default")
      (node (ref "R5") (pin "2") (pinfunction "2_2") (pintype "passive"))
      (node (ref "R6") (pin "2") (pinfunction "2_2") (pintype "passive"))
      (node (ref "U1") (pin "5") (pinfunction "FB_5") (pintype "passive"))
    )
    (net (code "51") (name "Net-(U1-SS)") (class "Default")
      (node (ref "C5") (pin "1") (pinfunction "1_1") (pintype "passive"))
      (node (ref "U1") (pin "8") (pinfunction "SS_8") (pintype "passive"))
    )
    (net (code "52") (name "Net-(U2-BST)") (class "Default")
      (node (ref "R14") (pin "2") (pinfunction "2_2") (pintype "passive"))
      (node (ref "U2") (pin "6") (pinfunction "BST_6") (pintype "passive"))
    )
    (net (code "53") (name "Net-(U2-EN)") (class "Default")
      (node (ref "R17") (pin "1") (pinfunction "1_1") (pintype "passive"))
      (node (ref "U2") (pin "5") (pinfunction "EN_5") (pintype "passive"))
    )
    (net (code "54") (name "Net-(U2-FB)") (class "Default")
      (node (ref "R18") (pin "2") (pinfunction "2_2") (pintype "passive"))
      (node (ref "U2") (pin "4") (pinfunction "FB_4") (pintype "passive"))
    )
    (net (code "55") (name "Net-(U2-SW)") (class "Default")
      (node (ref "C7") (pin "2") (pinfunction "2_2") (pintype "passive"))
      (node (ref "L2") (pin "1") (pinfunction "1_1") (pintype "passive"))
      (node (ref "U2") (pin "2") (pinfunction "SW_2") (pintype "passive"))
    )
    (net (code "56") (name "Net-(U3-CRS_DV{slash}MODE2)") (class "Default")
      (node (ref "R31") (pin "1") (pinfunction "1_1") (pintype "passive"))
      (node (ref "U3") (pin "11") (pinfunction "CRS_DV/MODE2_11") (pintype "passive"))
    )
    (net (code "57") (name "Net-(U3-RBSS)") (class "Default")
      (node (ref "R37") (pin "2") (pinfunction "2_2") (pintype "passive"))
      (node (ref "U3") (pin "24") (pinfunction "RBSS_24") (pintype "passive"))
    )
    (net (code "58") (name "Net-(U3-RXD0{slash}MODE0)") (class "Default")
      (node (ref "R29") (pin "1") (pinfunction "1_1") (pintype "passive"))
      (node (ref "U3") (pin "8") (pinfunction "RXD0/MODE0_8") (pintype "passive"))
    )
    (net (code "59") (name "Net-(U3-RXD1{slash}MODE1)") (class "Default")
      (node (ref "R30") (pin "1") (pinfunction "1_1") (pintype "passive"))
      (node (ref "U3") (pin "7") (pinfunction "RXD1/MODE1_7") (pintype "passive"))
    )
    (net (code "60") (name "Net-(U3-RXER{slash}PHYADO)") (class "Default")
      (node (ref "R32") (pin "1") (pinfunction "1_1") (pintype "passive"))
      (node (ref "U3") (pin "10") (pinfunction "RXER/PHYADO_10") (pintype "passive"))
    )
    (net (code "61") (name "Net-(U3-VDD2A)") (class "Default")
      (node (ref "C11") (pin "1") (pinfunction "1_1") (pintype "passive"))
      (node (ref "C12") (pin "1") (pinfunction "1_1") (pintype "passive"))
      (node (ref "C14") (pin "1") (pinfunction "1_1") (pintype "passive"))
      (node (ref "L3") (pin "2") (pinfunction "2_2") (pintype "passive"))
      (node (ref "R23") (pin "2") (pinfunction "2_2") (pintype "passive"))
      (node (ref "R24") (pin "2") (pinfunction "2_2") (pintype "passive"))
      (node (ref "R25") (pin "2") (pinfunction "2_2") (pintype "passive"))
      (node (ref "R26") (pin "2") (pinfunction "2_2") (pintype "passive"))
      (node (ref "U3") (pin "1") (pinfunction "VDD2A_1") (pintype "passive"))
      (node (ref "U3") (pin "19") (pinfunction "VIN50_19") (pintype "passive"))
    )
    (net (code "62") (name "Net-(U3-VDDCR)") (class "Default")
      (node (ref "C16") (pin "1") (pinfunction "1_1") (pintype "passive"))
      (node (ref "C17") (pin "1") (pintype "passive"))
      (node (ref "U3") (pin "6") (pinfunction "VDDCR_6") (pintype "passive"))
    )
    (net (code "63") (name "Net-(U3-XTAL)") (class "Default")
      (node (ref "C25") (pin "1") (pintype "passive"))
      (node (ref "TP7") (pin "1") (pinfunction "1_1") (pintype "passive"))
      (node (ref "U3") (pin "4") (pinfunction "XTAL_4") (pintype "passive"))
      (node (ref "Y1") (pin "2") (pintype "passive"))
    )
    (net (code "64") (name "Net-(U3-XTAL1)") (class "Default")
      (node (ref "C26") (pin "1") (pintype "passive"))
      (node (ref "U3") (pin "5") (pinfunction "XTAL1_5") (pintype "passive"))
      (node (ref "Y1") (pin "1") (pintype "passive"))
    )
    (net (code "65") (name "Net-(U3-nRTS)") (class "Default")
      (node (ref "C24") (pin "1") (pinfunction "1_1") (pintype "passive"))
      (node (ref "R36") (pin "1") (pinfunction "1_1") (pintype "passive"))
      (node (ref "U3") (pin "15") (pinfunction "nRTS_15") (pintype "passive"))
    )
    (net (code "66") (name "VCC=3.3V") (class "Default")
      (node (ref "C13") (pin "1") (pinfunction "1_1") (pintype "passive"))
      (node (ref "C15") (pin "1") (pinfunction "1_1") (pintype "passive"))
      (node (ref "C23") (pin "1") (pintype "passive"))
      (node (ref "L3") (pin "1") (pinfunction "1_1") (pintype "passive"))
      (node (ref "R19") (pin "1") (pinfunction "1_1") (pintype "passive"))
      (node (ref "R20") (pin "1") (pinfunction "1_1") (pintype "passive"))
      (node (ref "R22") (pin "2") (pinfunction "2_2") (pintype "passive"))
      (node (ref "R36") (pin "2") (pinfunction "2_2") (pintype "passive"))
      (node (ref "R38") (pin "2") (pinfunction "2_2") (pintype "passive"))
      (node (ref "R39") (pin "2") (pinfunction "2_2") (pintype "passive"))
      (node (ref "TrET1") (pin "2") (pinfunction "TDCT_2") (pintype "passive"))
      (node (ref "TrET1") (pin "7") (pinfunction "17_7") (pintype "passive"))
      (node (ref "U3") (pin "9") (pinfunction "VDDIO_9") (pintype "passive"))
    )
    (net (code "67") (name "VCC=5V") (class "Default")
      (node (ref "C2") (pin "1") (pinfunction "1_1") (pintype "passive"))
      (node (ref "C3") (pin "1") (pinfunction "1_1") (pintype "passive"))
      (node (ref "C8") (pin "1") (pinfunction "1_1") (pintype "passive"))
      (node (ref "C9") (pin "2") (pinfunction "2_2") (pintype "passive"))
      (node (ref "L1") (pin "2") (pinfunction "2_2") (pintype "passive"))
      (node (ref "R17") (pin "2") (pinfunction "2_2") (pintype "passive"))
      (node (ref "R2") (pin "1") (pinfunction "1_1") (pintype "passive"))
      (node (ref "R5") (pin "1") (pinfunction "1_1") (pintype "passive"))
      (node (ref "U2") (pin "3") (pinfunction "IN_3") (pintype "passive"))
    )
    (net (code "68") (name "unconnected-(R35-Pad1)") (class "Default")
      (node (ref "R35") (pin "1") (pinfunction "1_1") (pintype "passive"))
    )
  )
)
